# Stepper_module.net
KiCad netlist of a schematic drawn in EAGLE
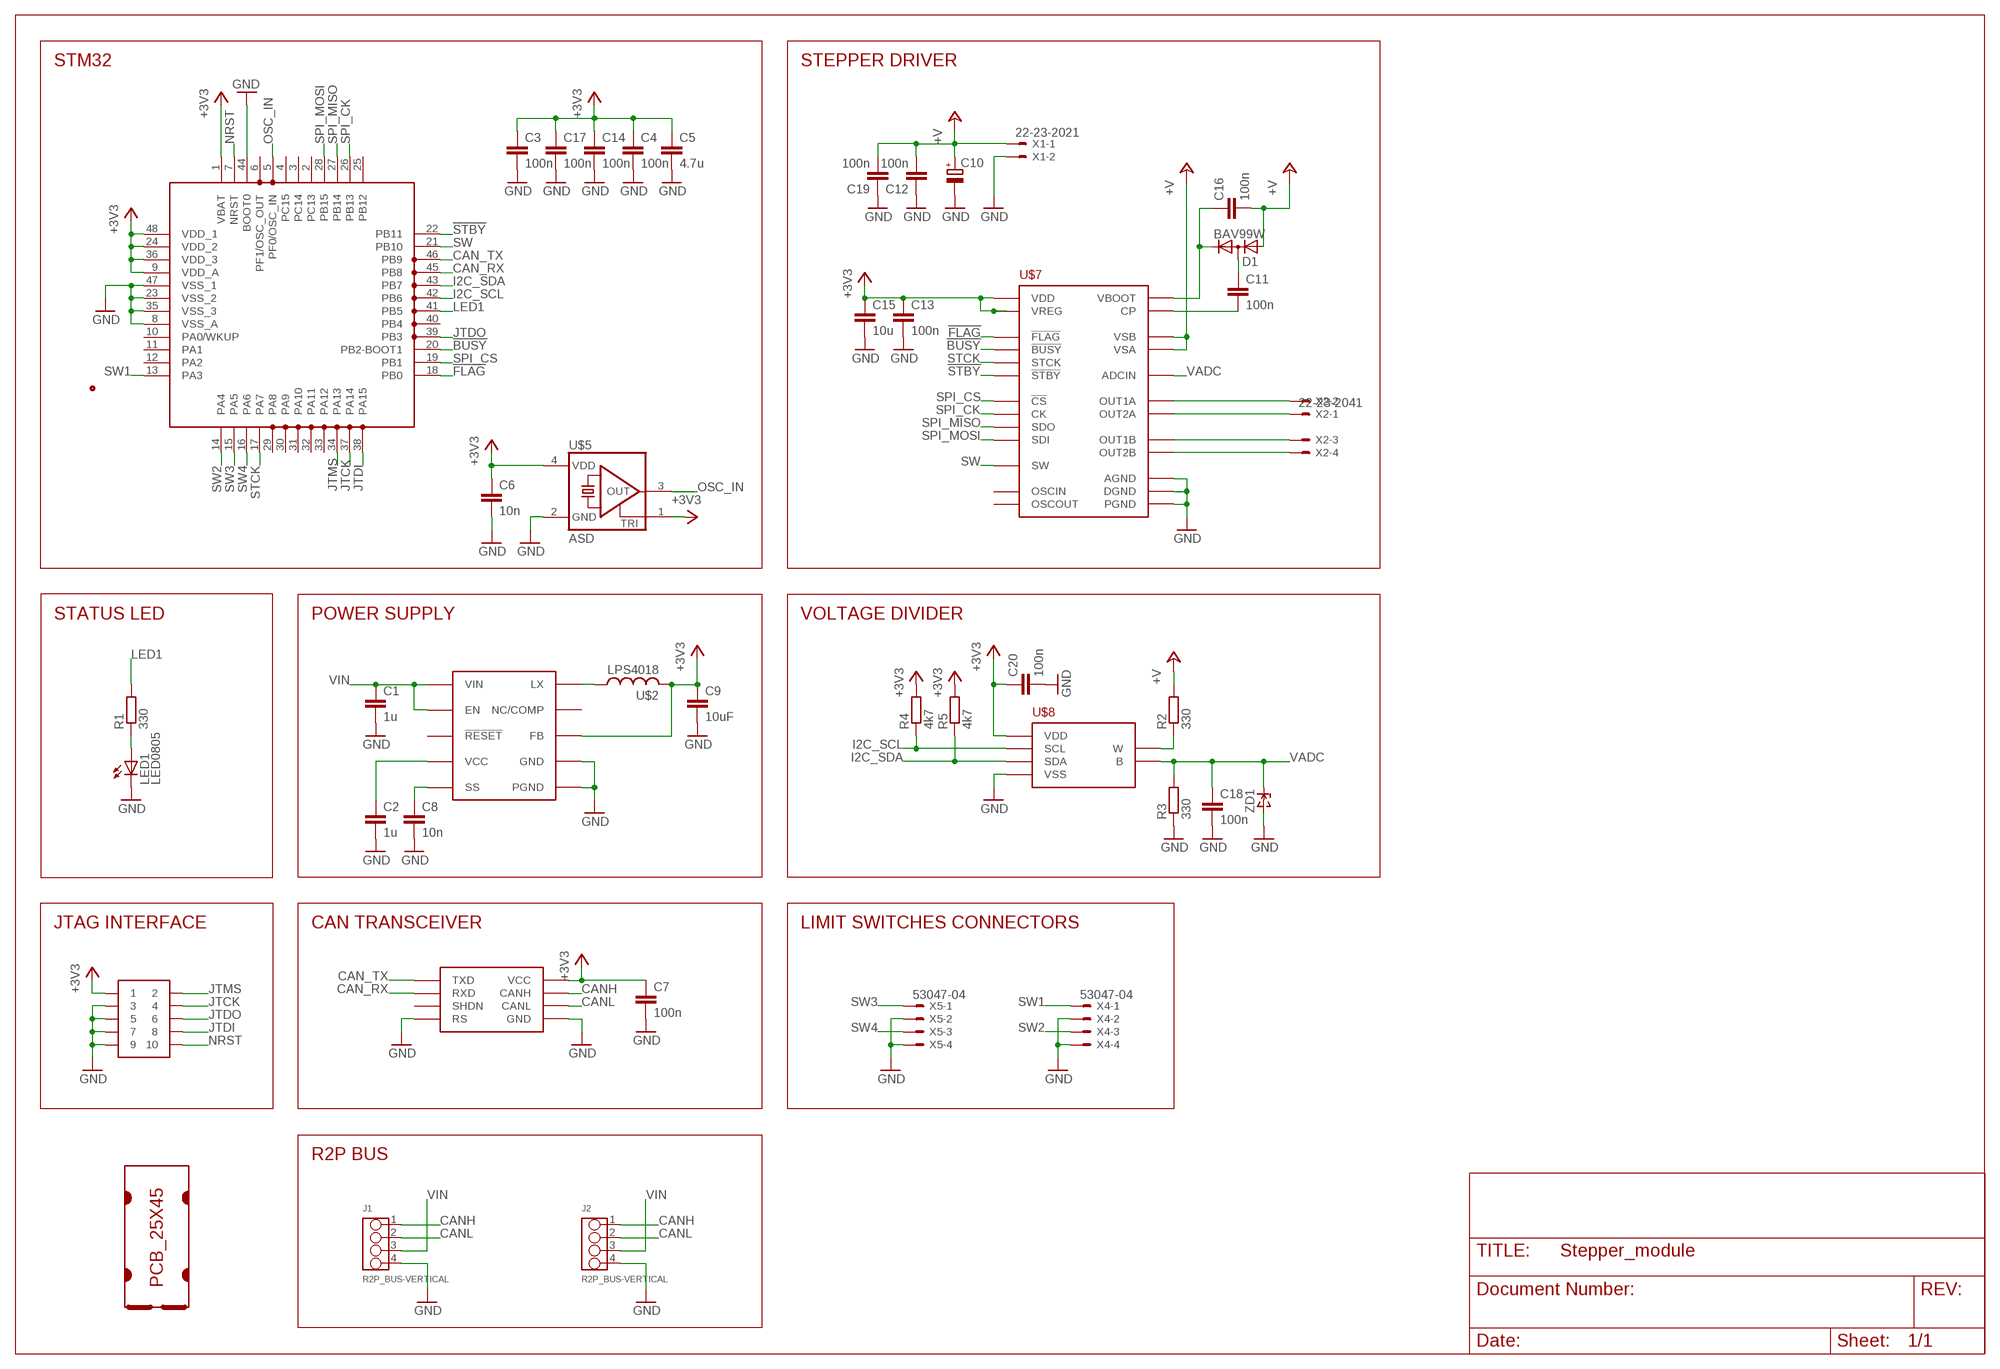
[diagram p0: schematic, sheet 1]

(export (version "E")
  (design (tool "Eeschema 10.0.6"))
  (components
    (comp (ref "C1")
      (value "1u")
      (footprint "eagle-import:C1206")
      (libsource (lib "eagle-import") (part "C1206"))
    )
    (comp (ref "C2")
      (value "1u")
      (footprint "eagle-import:C0603")
      (libsource (lib "eagle-import") (part "C0603"))
    )
    (comp (ref "C3")
      (value "100n")
      (footprint "eagle-import:C0603")
      (libsource (lib "eagle-import") (part "C0603"))
    )
    (comp (ref "C4")
      (value "100n")
      (footprint "eagle-import:C0603")
      (libsource (lib "eagle-import") (part "C0603"))
    )
    (comp (ref "C5")
      (value "4.7u")
      (footprint "eagle-import:C0805")
      (libsource (lib "eagle-import") (part "C0805"))
    )
    (comp (ref "C6")
      (value "10n")
      (footprint "eagle-import:C0603")
      (libsource (lib "eagle-import") (part "C0603"))
    )
    (comp (ref "C7")
      (value "100n")
      (footprint "eagle-import:C0603")
      (libsource (lib "eagle-import") (part "C0603"))
    )
    (comp (ref "C8")
      (value "10n")
      (footprint "eagle-import:C0603")
      (libsource (lib "eagle-import") (part "C0603"))
    )
    (comp (ref "C9")
      (value "10uF")
      (footprint "eagle-import:C0805")
      (libsource (lib "eagle-import") (part "C0805"))
    )
    (comp (ref "C10")
      (value "CPOL-EUD")
      (footprint "eagle-import:PANASONIC_D")
      (libsource (lib "eagle-import") (part "CPOL-EUD"))
    )
    (comp (ref "C11")
      (value "100n")
      (footprint "eagle-import:C0603")
      (libsource (lib "eagle-import") (part "C0603"))
    )
    (comp (ref "C12")
      (value "100n")
      (footprint "eagle-import:C0603")
      (libsource (lib "eagle-import") (part "C0603"))
    )
    (comp (ref "C13")
      (value "100n")
      (footprint "eagle-import:C0603")
      (libsource (lib "eagle-import") (part "C0603"))
    )
    (comp (ref "C14")
      (value "100n")
      (footprint "eagle-import:C0603")
      (libsource (lib "eagle-import") (part "C0603"))
    )
    (comp (ref "C15")
      (value "10u")
      (footprint "eagle-import:C0805")
      (libsource (lib "eagle-import") (part "C0805"))
    )
    (comp (ref "C16")
      (value "100n")
      (footprint "eagle-import:C0603")
      (libsource (lib "eagle-import") (part "C0603"))
    )
    (comp (ref "C17")
      (value "100n")
      (footprint "eagle-import:C0603")
      (libsource (lib "eagle-import") (part "C0603"))
    )
    (comp (ref "C18")
      (value "100n")
      (footprint "eagle-import:C0603")
      (libsource (lib "eagle-import") (part "C0603"))
    )
    (comp (ref "C19")
      (value "100n")
      (footprint "eagle-import:C0603")
      (libsource (lib "eagle-import") (part "C0603"))
    )
    (comp (ref "C20")
      (value "100n")
      (footprint "eagle-import:C0603")
      (libsource (lib "eagle-import") (part "C0603"))
    )
    (comp (ref "D1")
      (value "BAV99W")
      (footprint "eagle-import:SC70")
      (libsource (lib "eagle-import") (part "BAV99W"))
    )
    (comp (ref "J1")
      (value "R2P_BUS-VERTICAL")
      (footprint "eagle-import:OPL-EAGLE-LIBRARY_4P-2.0")
      (libsource (lib "eagle-import") (part "R2P_BUS-VERTICAL"))
    )
    (comp (ref "J2")
      (value "R2P_BUS-VERTICAL")
      (footprint "eagle-import:OPL-EAGLE-LIBRARY_4P-2.0")
      (libsource (lib "eagle-import") (part "R2P_BUS-VERTICAL"))
    )
    (comp (ref "LED1")
      (value "LED0805")
      (footprint "eagle-import:CHIPLED_0805")
      (libsource (lib "eagle-import") (part "LED0805"))
    )
    (comp (ref "R1")
      (value "330")
      (footprint "eagle-import:R0603")
      (libsource (lib "eagle-import") (part "R0603"))
    )
    (comp (ref "R2")
      (value "330")
      (footprint "eagle-import:R0603")
      (libsource (lib "eagle-import") (part "R0603"))
    )
    (comp (ref "R3")
      (value "330")
      (footprint "eagle-import:R0603")
      (libsource (lib "eagle-import") (part "R0603"))
    )
    (comp (ref "R4")
      (value "4k7")
      (footprint "eagle-import:R0603")
      (libsource (lib "eagle-import") (part "R0603"))
    )
    (comp (ref "R5")
      (value "4k7")
      (footprint "eagle-import:R0603")
      (libsource (lib "eagle-import") (part "R0603"))
    )
    (comp (ref "SOT1")
      (value "MAX3051EKA")
      (footprint "eagle-import:SOT23-8L")
      (libsource (lib "eagle-import") (part "MAX3051EKA"))
    )
    (comp (ref "U$1")
      (value "PCB_25X45")
      (footprint "eagle-import:25X45")
      (libsource (lib "eagle-import") (part "PCB_25X45"))
    )
    (comp (ref "U$2")
      (value "LPS4018")
      (footprint "eagle-import:LPS4018")
      (libsource (lib "eagle-import") (part "LPS4018"))
    )
    (comp (ref "U$3")
      (value "MAX17501")
      (footprint "eagle-import:TDFN-10")
      (libsource (lib "eagle-import") (part "MAX17501"))
    )
    (comp (ref "U$4")
      (value "JTAG-TH")
      (footprint "eagle-import:SAMTEC_FTSH-105-TH")
      (libsource (lib "eagle-import") (part "JTAG-TH"))
    )
    (comp (ref "U$5")
      (value "ASD")
      (footprint "eagle-import:2.5X2")
      (libsource (lib "eagle-import") (part "ASD"))
    )
    (comp (ref "U$6")
      (value "STM32F303C")
      (footprint "eagle-import:LQFP48")
      (libsource (lib "eagle-import") (part "STM32F303C"))
    )
    (comp (ref "U$7")
      (value "L6470")
      (footprint "eagle-import:HTSSOP28")
      (libsource (lib "eagle-import") (part "L6470"))
    )
    (comp (ref "U$8")
      (value "MCP4017")
      (footprint "eagle-import:SC70-6L")
      (libsource (lib "eagle-import") (part "MCP4017"))
    )
    (comp (ref "X1")
      (value "22-23-2021")
      (footprint "eagle-import:22-23-2021")
      (fields (field (name "MF") "MOLEX"))
      (libsource (lib "eagle-import") (part "22-23-2021"))
    )
    (comp (ref "X2")
      (value "22-23-2041")
      (footprint "eagle-import:22-23-2041")
      (fields (field (name "MF") "MOLEX"))
      (libsource (lib "eagle-import") (part "22-23-2041"))
    )
    (comp (ref "X4")
      (value "53047-04")
      (footprint "eagle-import:53047-04")
      (fields (field (name "MF") "WALDOM/MOLEX") (field (name "MPN") "53047-0410"))
      (libsource (lib "eagle-import") (part "53?-04047"))
    )
    (comp (ref "X5")
      (value "53047-04")
      (footprint "eagle-import:53047-04")
      (fields (field (name "MF") "WALDOM/MOLEX") (field (name "MPN") "53047-0410"))
      (libsource (lib "eagle-import") (part "53?-04047"))
    )
    (comp (ref "ZD1")
      (value "ZENERSOD-323F")
      (footprint "eagle-import:SOD-323F")
      (libsource (lib "eagle-import") (part "ZENERSOD-323F"))
    )
  )
  (nets
    (net (code "1") (name "+3V3") (class "Default")
      (node (ref "C13") (pin "1") (pinfunction "1_1") (pintype "passive"))
      (node (ref "C14") (pin "1") (pinfunction "1_1") (pintype "passive"))
      (node (ref "C15") (pin "1") (pinfunction "1_1") (pintype "passive"))
      (node (ref "C17") (pin "1") (pinfunction "1_1") (pintype "passive"))
      (node (ref "C20") (pin "1") (pinfunction "1_1") (pintype "passive"))
      (node (ref "C3") (pin "1") (pinfunction "1_1") (pintype "passive"))
      (node (ref "C4") (pin "1") (pinfunction "1_1") (pintype "passive"))
      (node (ref "C5") (pin "1") (pinfunction "1_1") (pintype "passive"))
      (node (ref "C6") (pin "1") (pinfunction "1_1") (pintype "passive"))
      (node (ref "C7") (pin "1") (pinfunction "1_1") (pintype "passive"))
      (node (ref "C9") (pin "1") (pinfunction "1_1") (pintype "passive"))
      (node (ref "R4") (pin "2") (pinfunction "2_2") (pintype "passive"))
      (node (ref "R5") (pin "2") (pinfunction "2_2") (pintype "passive"))
      (node (ref "SOT1") (pin "3") (pinfunction "VCC_3") (pintype "bidirectional"))
      (node (ref "U$2") (pin "P$2") (pinfunction "2_P$2") (pintype "passive"))
      (node (ref "U$3") (pin "P$5") (pinfunction "FB_P$5") (pintype "bidirectional"))
      (node (ref "U$4") (pin "1") (pinfunction "1_1") (pintype "bidirectional"))
      (node (ref "U$5") (pin "1") (pinfunction "TRI_1") (pintype "input"))
      (node (ref "U$5") (pin "4") (pinfunction "VDD_4") (pintype "power_in"))
      (node (ref "U$6") (pin "1") (pinfunction "VBAT_1") (pintype "bidirectional"))
      (node (ref "U$6") (pin "24") (pinfunction "VDD_2_24") (pintype "bidirectional"))
      (node (ref "U$6") (pin "36") (pinfunction "VDD_3_36") (pintype "bidirectional"))
      (node (ref "U$6") (pin "48") (pinfunction "VDD_1_48") (pintype "bidirectional"))
      (node (ref "U$6") (pin "9") (pinfunction "VDD_A_9") (pintype "bidirectional"))
      (node (ref "U$7") (pin "P$17") (pinfunction "VDD_P$17") (pintype "bidirectional"))
      (node (ref "U$7") (pin "P$6") (pinfunction "VREG_P$6") (pintype "bidirectional"))
      (node (ref "U$8") (pin "1") (pinfunction "VDD_1") (pintype "bidirectional"))
    )
    (net (code "2") (name "+V") (class "Default")
      (node (ref "C10") (pin "+") (pinfunction "+_+") (pintype "passive"))
      (node (ref "C12") (pin "2") (pinfunction "2_2") (pintype "passive"))
      (node (ref "C16") (pin "2") (pinfunction "2_2") (pintype "passive"))
      (node (ref "C19") (pin "2") (pinfunction "2_2") (pintype "passive"))
      (node (ref "D1") (pin "1") (pinfunction "A_1") (pintype "passive"))
      (node (ref "R2") (pin "2") (pinfunction "2_2") (pintype "passive"))
      (node (ref "U$7") (pin "P$12") (pinfunction "VSB_P$12") (pintype "bidirectional"))
      (node (ref "U$7") (pin "P$16") (pinfunction "VSB_P$16") (pintype "bidirectional"))
      (node (ref "U$7") (pin "P$2") (pinfunction "VSA_P$2") (pintype "bidirectional"))
      (node (ref "U$7") (pin "P$26") (pinfunction "VSA_P$26") (pintype "bidirectional"))
      (node (ref "X1") (pin "1") (pinfunction "S_1") (pintype "passive"))
    )
    (net (code "3") (name "/CANH") (class "Default")
      (node (ref "J1") (pin "1") (pinfunction "1_1") (pintype "bidirectional"))
      (node (ref "J2") (pin "1") (pinfunction "1_1") (pintype "bidirectional"))
      (node (ref "SOT1") (pin "7") (pinfunction "CANH_7") (pintype "bidirectional"))
    )
    (net (code "4") (name "/CANL") (class "Default")
      (node (ref "J1") (pin "2") (pinfunction "2_2") (pintype "bidirectional"))
      (node (ref "J2") (pin "2") (pinfunction "2_2") (pintype "bidirectional"))
      (node (ref "SOT1") (pin "6") (pinfunction "CANL_6") (pintype "bidirectional"))
    )
    (net (code "5") (name "/CAN_RX") (class "Default")
      (node (ref "SOT1") (pin "4") (pinfunction "RXD_4") (pintype "bidirectional"))
      (node (ref "U$6") (pin "45") (pinfunction "PB8_45") (pintype "bidirectional"))
    )
    (net (code "6") (name "/CAN_TX") (class "Default")
      (node (ref "SOT1") (pin "1") (pinfunction "TXD_1") (pintype "bidirectional"))
      (node (ref "U$6") (pin "46") (pinfunction "PB9_46") (pintype "bidirectional"))
    )
    (net (code "7") (name "/I2C_SCL") (class "Default")
      (node (ref "R4") (pin "1") (pinfunction "1_1") (pintype "passive"))
      (node (ref "U$6") (pin "42") (pinfunction "PB6_42") (pintype "bidirectional"))
      (node (ref "U$8") (pin "3") (pinfunction "SCL_3") (pintype "bidirectional"))
    )
    (net (code "8") (name "/I2C_SDA") (class "Default")
      (node (ref "R5") (pin "1") (pinfunction "1_1") (pintype "passive"))
      (node (ref "U$6") (pin "43") (pinfunction "PB7_43") (pintype "bidirectional"))
      (node (ref "U$8") (pin "4") (pinfunction "SDA_4") (pintype "bidirectional"))
    )
    (net (code "9") (name "/JTCK") (class "Default")
      (node (ref "U$4") (pin "4") (pinfunction "4_4") (pintype "bidirectional"))
      (node (ref "U$6") (pin "37") (pinfunction "PA14_37") (pintype "bidirectional"))
    )
    (net (code "10") (name "/JTDI") (class "Default")
      (node (ref "U$4") (pin "8") (pinfunction "8_8") (pintype "bidirectional"))
      (node (ref "U$6") (pin "38") (pinfunction "PA15_38") (pintype "bidirectional"))
    )
    (net (code "11") (name "/JTDO") (class "Default")
      (node (ref "U$4") (pin "6") (pinfunction "6_6") (pintype "bidirectional"))
      (node (ref "U$6") (pin "39") (pinfunction "PB3_39") (pintype "bidirectional"))
    )
    (net (code "12") (name "/JTMS") (class "Default")
      (node (ref "U$4") (pin "2") (pinfunction "2_2") (pintype "bidirectional"))
      (node (ref "U$6") (pin "34") (pinfunction "PA13_34") (pintype "bidirectional"))
    )
    (net (code "13") (name "/LED1") (class "Default")
      (node (ref "R1") (pin "2") (pinfunction "2_2") (pintype "passive"))
      (node (ref "U$6") (pin "41") (pinfunction "PB5_41") (pintype "bidirectional"))
    )
    (net (code "14") (name "/NRST") (class "Default")
      (node (ref "U$4") (pin "10") (pinfunction "10_10") (pintype "bidirectional"))
      (node (ref "U$6") (pin "7") (pinfunction "NRST_7") (pintype "bidirectional"))
    )
    (net (code "15") (name "/OSC_IN") (class "Default")
      (node (ref "U$5") (pin "3") (pinfunction "OUT_3") (pintype "output"))
      (node (ref "U$6") (pin "5") (pinfunction "PF0/OSC_IN_5") (pintype "bidirectional"))
    )
    (net (code "16") (name "/SPI_CK") (class "Default")
      (node (ref "U$6") (pin "26") (pinfunction "PB13_26") (pintype "bidirectional"))
      (node (ref "U$7") (pin "P$19") (pinfunction "CK_P$19") (pintype "bidirectional"))
    )
    (net (code "17") (name "/SPI_CS") (class "Default")
      (node (ref "U$6") (pin "19") (pinfunction "PB1_19") (pintype "bidirectional"))
      (node (ref "U$7") (pin "P$23") (pinfunction "~{CS}_P$23") (pintype "bidirectional"))
    )
    (net (code "18") (name "/SPI_MISO") (class "Default")
      (node (ref "U$6") (pin "27") (pinfunction "PB14_27") (pintype "bidirectional"))
      (node (ref "U$7") (pin "P$18") (pinfunction "SDO_P$18") (pintype "bidirectional"))
    )
    (net (code "19") (name "/SPI_MOSI") (class "Default")
      (node (ref "U$6") (pin "28") (pinfunction "PB15_28") (pintype "bidirectional"))
      (node (ref "U$7") (pin "P$20") (pinfunction "SDI_P$20") (pintype "bidirectional"))
    )
    (net (code "20") (name "/STCK") (class "Default")
      (node (ref "U$6") (pin "17") (pinfunction "PA7_17") (pintype "bidirectional"))
      (node (ref "U$7") (pin "P$25") (pinfunction "STCK_P$25") (pintype "bidirectional"))
    )
    (net (code "21") (name "/SW") (class "Default")
      (node (ref "U$6") (pin "21") (pinfunction "PB10_21") (pintype "bidirectional"))
      (node (ref "U$7") (pin "P$4") (pinfunction "SW_P$4") (pintype "bidirectional"))
    )
    (net (code "22") (name "/SW1") (class "Default")
      (node (ref "U$6") (pin "13") (pinfunction "PA3_13") (pintype "bidirectional"))
      (node (ref "X4") (pin "1") (pinfunction "S_1") (pintype "passive"))
    )
    (net (code "23") (name "/SW2") (class "Default")
      (node (ref "U$6") (pin "14") (pinfunction "PA4_14") (pintype "bidirectional"))
      (node (ref "X4") (pin "3") (pinfunction "S_3") (pintype "passive"))
    )
    (net (code "24") (name "/SW3") (class "Default")
      (node (ref "U$6") (pin "15") (pinfunction "PA5_15") (pintype "bidirectional"))
      (node (ref "X5") (pin "1") (pinfunction "S_1") (pintype "passive"))
    )
    (net (code "25") (name "/SW4") (class "Default")
      (node (ref "U$6") (pin "16") (pinfunction "PA6_16") (pintype "bidirectional"))
      (node (ref "X5") (pin "3") (pinfunction "S_3") (pintype "passive"))
    )
    (net (code "26") (name "/VADC") (class "Default")
      (node (ref "C18") (pin "1") (pinfunction "1_1") (pintype "passive"))
      (node (ref "R3") (pin "2") (pinfunction "2_2") (pintype "passive"))
      (node (ref "U$7") (pin "P$5") (pinfunction "ADCIN_P$5") (pintype "bidirectional"))
      (node (ref "U$8") (pin "5") (pinfunction "B_5") (pintype "bidirectional"))
      (node (ref "ZD1") (pin "C") (pinfunction "C_C") (pintype "passive"))
    )
    (net (code "27") (name "/VIN") (class "Default")
      (node (ref "C1") (pin "1") (pinfunction "1_1") (pintype "passive"))
      (node (ref "J1") (pin "3") (pinfunction "3_3") (pintype "bidirectional"))
      (node (ref "J2") (pin "3") (pinfunction "3_3") (pintype "bidirectional"))
      (node (ref "U$3") (pin "P$2") (pinfunction "VIN_P$2") (pintype "bidirectional"))
      (node (ref "U$3") (pin "P$3") (pinfunction "EN_P$3") (pintype "bidirectional"))
    )
    (net (code "28") (name "/~{BUSY}") (class "Default")
      (node (ref "U$6") (pin "20") (pinfunction "PB2-BOOT1_20") (pintype "bidirectional"))
      (node (ref "U$7") (pin "P$22") (pinfunction "~{BUSY}_P$22") (pintype "bidirectional"))
    )
    (net (code "29") (name "/~{FLAG}") (class "Default")
      (node (ref "U$6") (pin "18") (pinfunction "PB0_18") (pintype "bidirectional"))
      (node (ref "U$7") (pin "P$24") (pinfunction "~{FLAG}_P$24") (pintype "bidirectional"))
    )
    (net (code "30") (name "/~{STBY}") (class "Default")
      (node (ref "U$6") (pin "22") (pinfunction "PB11_22") (pintype "bidirectional"))
      (node (ref "U$7") (pin "P$3") (pinfunction "~{STBY}_P$3") (pintype "bidirectional"))
    )
    (net (code "31") (name "GND") (class "Default")
      (node (ref "C1") (pin "2") (pinfunction "2_2") (pintype "passive"))
      (node (ref "C10") (pin "-") (pinfunction "-_-") (pintype "passive"))
      (node (ref "C12") (pin "1") (pinfunction "1_1") (pintype "passive"))
      (node (ref "C13") (pin "2") (pinfunction "2_2") (pintype "passive"))
      (node (ref "C14") (pin "2") (pinfunction "2_2") (pintype "passive"))
      (node (ref "C15") (pin "2") (pinfunction "2_2") (pintype "passive"))
      (node (ref "C17") (pin "2") (pinfunction "2_2") (pintype "passive"))
      (node (ref "C18") (pin "2") (pinfunction "2_2") (pintype "passive"))
      (node (ref "C19") (pin "1") (pinfunction "1_1") (pintype "passive"))
      (node (ref "C2") (pin "2") (pinfunction "2_2") (pintype "passive"))
      (node (ref "C20") (pin "2") (pinfunction "2_2") (pintype "passive"))
      (node (ref "C3") (pin "2") (pinfunction "2_2") (pintype "passive"))
      (node (ref "C4") (pin "2") (pinfunction "2_2") (pintype "passive"))
      (node (ref "C5") (pin "2") (pinfunction "2_2") (pintype "passive"))
      (node (ref "C6") (pin "2") (pinfunction "2_2") (pintype "passive"))
      (node (ref "C7") (pin "2") (pinfunction "2_2") (pintype "passive"))
      (node (ref "C8") (pin "2") (pinfunction "2_2") (pintype "passive"))
      (node (ref "C9") (pin "2") (pinfunction "2_2") (pintype "passive"))
      (node (ref "J1") (pin "4") (pinfunction "4_4") (pintype "bidirectional"))
      (node (ref "J2") (pin "4") (pinfunction "4_4") (pintype "bidirectional"))
      (node (ref "LED1") (pin "C") (pinfunction "C_C") (pintype "passive"))
      (node (ref "R3") (pin "1") (pinfunction "1_1") (pintype "passive"))
      (node (ref "SOT1") (pin "2") (pinfunction "GND_2") (pintype "bidirectional"))
      (node (ref "SOT1") (pin "8") (pinfunction "RS_8") (pintype "bidirectional"))
      (node (ref "U$3") (pin "P$1") (pinfunction "PGND_P$1") (pintype "bidirectional"))
      (node (ref "U$3") (pin "P$11") (pinfunction "PGND_P$11") (pintype "bidirectional"))
      (node (ref "U$3") (pin "P$9") (pinfunction "GND_P$9") (pintype "bidirectional"))
      (node (ref "U$4") (pin "3") (pinfunction "3_3") (pintype "bidirectional"))
      (node (ref "U$4") (pin "5") (pinfunction "5_5") (pintype "bidirectional"))
      (node (ref "U$4") (pin "7") (pinfunction "7_7") (pintype "bidirectional"))
      (node (ref "U$4") (pin "9") (pinfunction "9_9") (pintype "bidirectional"))
      (node (ref "U$5") (pin "2") (pinfunction "GND_2") (pintype "power_in"))
      (node (ref "U$6") (pin "23") (pinfunction "VSS_2_23") (pintype "bidirectional"))
      (node (ref "U$6") (pin "35") (pinfunction "VSS_3_35") (pintype "bidirectional"))
      (node (ref "U$6") (pin "44") (pinfunction "BOOT0_44") (pintype "bidirectional"))
      (node (ref "U$6") (pin "47") (pinfunction "VSS_1_47") (pintype "bidirectional"))
      (node (ref "U$6") (pin "8") (pinfunction "VSS_A_8") (pintype "bidirectional"))
      (node (ref "U$7") (pin "P$13") (pinfunction "PGND_P$13") (pintype "bidirectional"))
      (node (ref "U$7") (pin "P$21") (pinfunction "DGND_P$21") (pintype "bidirectional"))
      (node (ref "U$7") (pin "P$27") (pinfunction "PGND_P$27") (pintype "bidirectional"))
      (node (ref "U$7") (pin "P$29") (pinfunction "PGND_P$29") (pintype "bidirectional"))
      (node (ref "U$7") (pin "P$9") (pinfunction "AGND_P$9") (pintype "bidirectional"))
      (node (ref "U$8") (pin "2") (pinfunction "VSS_2") (pintype "bidirectional"))
      (node (ref "X1") (pin "2") (pinfunction "S_2") (pintype "passive"))
      (node (ref "X4") (pin "2") (pinfunction "S_2") (pintype "passive"))
      (node (ref "X4") (pin "4") (pinfunction "S_4") (pintype "passive"))
      (node (ref "X5") (pin "2") (pinfunction "S_2") (pintype "passive"))
      (node (ref "X5") (pin "4") (pinfunction "S_4") (pintype "passive"))
      (node (ref "ZD1") (pin "A") (pinfunction "A_A") (pintype "passive"))
    )
    (net (code "32") (name "Net-(D1-AC)") (class "Default")
      (node (ref "C11") (pin "1") (pinfunction "1_1") (pintype "passive"))
      (node (ref "D1") (pin "3") (pinfunction "AC_3") (pintype "passive"))
    )
    (net (code "33") (name "Net-(D1-C)") (class "Default")
      (node (ref "C16") (pin "1") (pinfunction "1_1") (pintype "passive"))
      (node (ref "D1") (pin "2") (pinfunction "C_2") (pintype "passive"))
      (node (ref "U$7") (pin "P$11") (pinfunction "VBOOT_P$11") (pintype "bidirectional"))
    )
    (net (code "34") (name "Net-(LED1-PadA)") (class "Default")
      (node (ref "LED1") (pin "A") (pinfunction "A_A") (pintype "passive"))
      (node (ref "R1") (pin "1") (pinfunction "1_1") (pintype "passive"))
    )
    (net (code "35") (name "Net-(U$2-1)") (class "Default")
      (node (ref "U$2") (pin "P$1") (pinfunction "1_P$1") (pintype "passive"))
      (node (ref "U$3") (pin "P$10") (pinfunction "LX_P$10") (pintype "bidirectional"))
    )
    (net (code "36") (name "Net-(U$3-SS)") (class "Default")
      (node (ref "C8") (pin "1") (pinfunction "1_1") (pintype "passive"))
      (node (ref "U$3") (pin "P$6") (pinfunction "SS_P$6") (pintype "bidirectional"))
    )
    (net (code "37") (name "Net-(U$3-VCC)") (class "Default")
      (node (ref "C2") (pin "1") (pinfunction "1_1") (pintype "passive"))
      (node (ref "U$3") (pin "P$4") (pinfunction "VCC_P$4") (pintype "bidirectional"))
    )
    (net (code "38") (name "Net-(U$7-CP)") (class "Default")
      (node (ref "C11") (pin "2") (pinfunction "2_2") (pintype "passive"))
      (node (ref "U$7") (pin "P$10") (pinfunction "CP_P$10") (pintype "bidirectional"))
    )
    (net (code "39") (name "Net-(U$7-OUT1A)") (class "Default")
      (node (ref "U$7") (pin "P$1") (pinfunction "OUT1A_P$1") (pintype "bidirectional"))
      (node (ref "X2") (pin "2") (pinfunction "S_2") (pintype "passive"))
    )
    (net (code "40") (name "Net-(U$7-OUT1B)") (class "Default")
      (node (ref "U$7") (pin "P$14") (pinfunction "OUT1B_P$14") (pintype "bidirectional"))
      (node (ref "X2") (pin "3") (pinfunction "S_3") (pintype "passive"))
    )
    (net (code "41") (name "Net-(U$7-OUT2A)") (class "Default")
      (node (ref "U$7") (pin "P$28") (pinfunction "OUT2A_P$28") (pintype "bidirectional"))
      (node (ref "X2") (pin "1") (pinfunction "S_1") (pintype "passive"))
    )
    (net (code "42") (name "Net-(U$7-OUT2B)") (class "Default")
      (node (ref "U$7") (pin "P$15") (pinfunction "OUT2B_P$15") (pintype "bidirectional"))
      (node (ref "X2") (pin "4") (pinfunction "S_4") (pintype "passive"))
    )
    (net (code "43") (name "Net-(U$8-W)") (class "Default")
      (node (ref "R2") (pin "1") (pinfunction "1_1") (pintype "passive"))
      (node (ref "U$8") (pin "6") (pinfunction "W_6") (pintype "bidirectional"))
    )
    (net (code "44") (name "unconnected-(SOT1-SHDN-Pad5)") (class "Default")
      (node (ref "SOT1") (pin "5") (pinfunction "SHDN_5") (pintype "bidirectional"))
    )
    (net (code "45") (name "unconnected-(U$3-NC{slash}COMP-PadP$7)") (class "Default")
      (node (ref "U$3") (pin "P$7") (pinfunction "NC/COMP_P$7") (pintype "bidirectional"))
    )
    (net (code "46") (name "unconnected-(U$3-~{RESET}-PadP$8)") (class "Default")
      (node (ref "U$3") (pin "P$8") (pinfunction "~{RESET}_P$8") (pintype "bidirectional"))
    )
    (net (code "47") (name "unconnected-(U$6-PA0{slash}WKUP-Pad10)") (class "Default")
      (node (ref "U$6") (pin "10") (pinfunction "PA0/WKUP_10") (pintype "bidirectional"))
    )
    (net (code "48") (name "unconnected-(U$6-PA1-Pad11)") (class "Default")
      (node (ref "U$6") (pin "11") (pinfunction "PA1_11") (pintype "bidirectional"))
    )
    (net (code "49") (name "unconnected-(U$6-PA2-Pad12)") (class "Default")
      (node (ref "U$6") (pin "12") (pinfunction "PA2_12") (pintype "bidirectional"))
    )
    (net (code "50") (name "unconnected-(U$6-PA8-Pad29)") (class "Default")
      (node (ref "U$6") (pin "29") (pinfunction "PA8_29") (pintype "bidirectional"))
    )
    (net (code "51") (name "unconnected-(U$6-PA9-Pad30)") (class "Default")
      (node (ref "U$6") (pin "30") (pinfunction "PA9_30") (pintype "bidirectional"))
    )
    (net (code "52") (name "unconnected-(U$6-PA10-Pad31)") (class "Default")
      (node (ref "U$6") (pin "31") (pinfunction "PA10_31") (pintype "bidirectional"))
    )
    (net (code "53") (name "unconnected-(U$6-PA11-Pad32)") (class "Default")
      (node (ref "U$6") (pin "32") (pinfunction "PA11_32") (pintype "bidirectional"))
    )
    (net (code "54") (name "unconnected-(U$6-PA12-Pad33)") (class "Default")
      (node (ref "U$6") (pin "33") (pinfunction "PA12_33") (pintype "bidirectional"))
    )
    (net (code "55") (name "unconnected-(U$6-PB4-Pad40)") (class "Default")
      (node (ref "U$6") (pin "40") (pinfunction "PB4_40") (pintype "bidirectional"))
    )
    (net (code "56") (name "unconnected-(U$6-PB12-Pad25)") (class "Default")
      (node (ref "U$6") (pin "25") (pinfunction "PB12_25") (pintype "bidirectional"))
    )
    (net (code "57") (name "unconnected-(U$6-PC13-Pad2)") (class "Default")
      (node (ref "U$6") (pin "2") (pinfunction "PC13_2") (pintype "bidirectional"))
    )
    (net (code "58") (name "unconnected-(U$6-PC14-Pad3)") (class "Default")
      (node (ref "U$6") (pin "3") (pinfunction "PC14_3") (pintype "bidirectional"))
    )
    (net (code "59") (name "unconnected-(U$6-PC15-Pad4)") (class "Default")
      (node (ref "U$6") (pin "4") (pinfunction "PC15_4") (pintype "bidirectional"))
    )
    (net (code "60") (name "unconnected-(U$6-PF1{slash}OSC_OUT-Pad6)") (class "Default")
      (node (ref "U$6") (pin "6") (pinfunction "PF1/OSC_OUT_6") (pintype "bidirectional"))
    )
    (net (code "61") (name "unconnected-(U$7-OSCIN-PadP$7)") (class "Default")
      (node (ref "U$7") (pin "P$7") (pinfunction "OSCIN_P$7") (pintype "bidirectional"))
    )
    (net (code "62") (name "unconnected-(U$7-OSCOUT-PadP$8)") (class "Default")
      (node (ref "U$7") (pin "P$8") (pinfunction "OSCOUT_P$8") (pintype "bidirectional"))
    )
  )
)
